# 7seg.net
KiCad netlist of a schematic drawn in Altium Designer
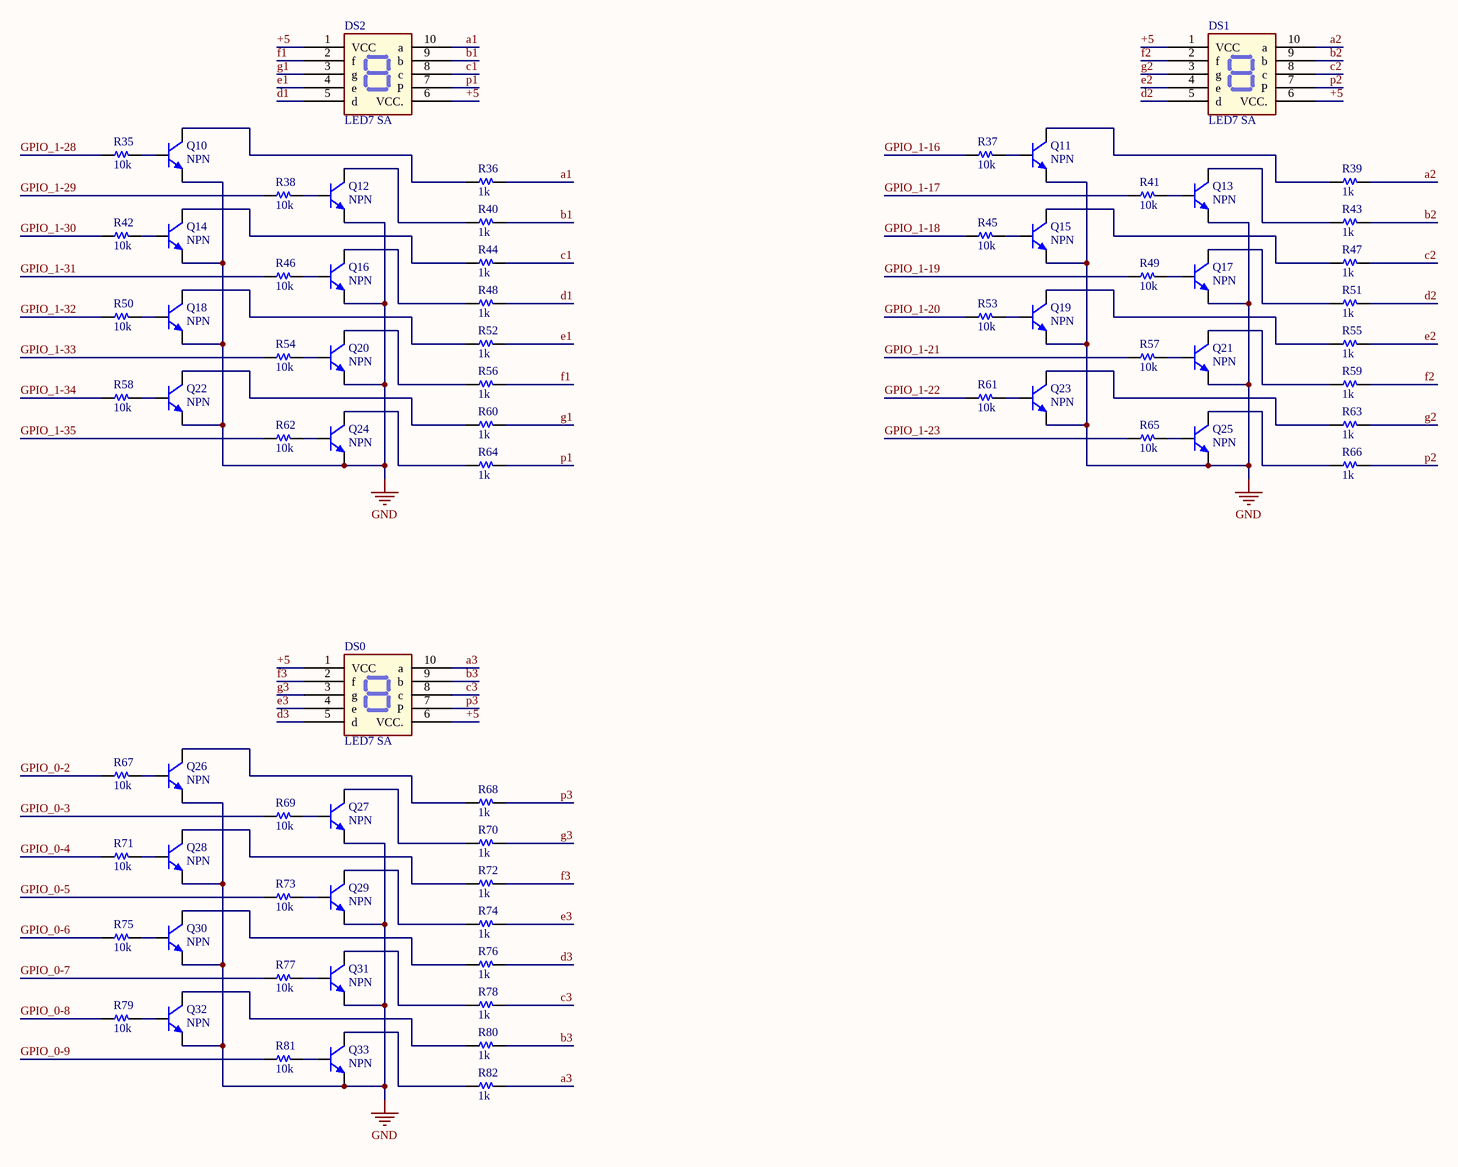
[diagram p0: 7seg.SchDoc]

(export (version "E")
  (design (tool "Eeschema 10.0.6"))
  (components
    (comp (ref "DS0")
      (value "LED7 SA")
      (footprint "Led7seg 0.36in")
      (libsource (lib "chipfc_libs") (part "LED7 SA"))
    )
    (comp (ref "DS1")
      (value "LED7 SA")
      (footprint "Led7seg 0.36in")
      (libsource (lib "chipfc_libs") (part "LED7 SA"))
    )
    (comp (ref "DS2")
      (value "LED7 SA")
      (footprint "Led7seg 0.36in")
      (libsource (lib "chipfc_libs") (part "LED7 SA"))
    )
    (comp (ref "Q10")
      (value "NPN")
      (footprint "SOT-23")
      (description "NPN Bipolar Transistor")
      (libsource (lib "chipfc_libs") (part "Transistor NPN"))
    )
    (comp (ref "Q11")
      (value "NPN")
      (footprint "SOT-23")
      (description "NPN Bipolar Transistor")
      (libsource (lib "chipfc_libs") (part "Transistor NPN"))
    )
    (comp (ref "Q12")
      (value "NPN")
      (footprint "SOT-23")
      (description "NPN Bipolar Transistor")
      (libsource (lib "chipfc_libs") (part "Transistor NPN"))
    )
    (comp (ref "Q13")
      (value "NPN")
      (footprint "SOT-23")
      (description "NPN Bipolar Transistor")
      (libsource (lib "chipfc_libs") (part "Transistor NPN"))
    )
    (comp (ref "Q14")
      (value "NPN")
      (footprint "SOT-23")
      (description "NPN Bipolar Transistor")
      (libsource (lib "chipfc_libs") (part "Transistor NPN"))
    )
    (comp (ref "Q15")
      (value "NPN")
      (footprint "SOT-23")
      (description "NPN Bipolar Transistor")
      (libsource (lib "chipfc_libs") (part "Transistor NPN"))
    )
    (comp (ref "Q16")
      (value "NPN")
      (footprint "SOT-23")
      (description "NPN Bipolar Transistor")
      (libsource (lib "chipfc_libs") (part "Transistor NPN"))
    )
    (comp (ref "Q17")
      (value "NPN")
      (footprint "SOT-23")
      (description "NPN Bipolar Transistor")
      (libsource (lib "chipfc_libs") (part "Transistor NPN"))
    )
    (comp (ref "Q18")
      (value "NPN")
      (footprint "SOT-23")
      (description "NPN Bipolar Transistor")
      (libsource (lib "chipfc_libs") (part "Transistor NPN"))
    )
    (comp (ref "Q19")
      (value "NPN")
      (footprint "SOT-23")
      (description "NPN Bipolar Transistor")
      (libsource (lib "chipfc_libs") (part "Transistor NPN"))
    )
    (comp (ref "Q20")
      (value "NPN")
      (footprint "SOT-23")
      (description "NPN Bipolar Transistor")
      (libsource (lib "chipfc_libs") (part "Transistor NPN"))
    )
    (comp (ref "Q21")
      (value "NPN")
      (footprint "SOT-23")
      (description "NPN Bipolar Transistor")
      (libsource (lib "chipfc_libs") (part "Transistor NPN"))
    )
    (comp (ref "Q22")
      (value "NPN")
      (footprint "SOT-23")
      (description "NPN Bipolar Transistor")
      (libsource (lib "chipfc_libs") (part "Transistor NPN"))
    )
    (comp (ref "Q23")
      (value "NPN")
      (footprint "SOT-23")
      (description "NPN Bipolar Transistor")
      (libsource (lib "chipfc_libs") (part "Transistor NPN"))
    )
    (comp (ref "Q24")
      (value "NPN")
      (footprint "SOT-23")
      (description "NPN Bipolar Transistor")
      (libsource (lib "chipfc_libs") (part "Transistor NPN"))
    )
    (comp (ref "Q25")
      (value "NPN")
      (footprint "SOT-23")
      (description "NPN Bipolar Transistor")
      (libsource (lib "chipfc_libs") (part "Transistor NPN"))
    )
    (comp (ref "Q26")
      (value "NPN")
      (footprint "SOT-23")
      (description "NPN Bipolar Transistor")
      (libsource (lib "chipfc_libs") (part "Transistor NPN"))
    )
    (comp (ref "Q27")
      (value "NPN")
      (footprint "SOT-23")
      (description "NPN Bipolar Transistor")
      (libsource (lib "chipfc_libs") (part "Transistor NPN"))
    )
    (comp (ref "Q28")
      (value "NPN")
      (footprint "SOT-23")
      (description "NPN Bipolar Transistor")
      (libsource (lib "chipfc_libs") (part "Transistor NPN"))
    )
    (comp (ref "Q29")
      (value "NPN")
      (footprint "SOT-23")
      (description "NPN Bipolar Transistor")
      (libsource (lib "chipfc_libs") (part "Transistor NPN"))
    )
    (comp (ref "Q30")
      (value "NPN")
      (footprint "SOT-23")
      (description "NPN Bipolar Transistor")
      (libsource (lib "chipfc_libs") (part "Transistor NPN"))
    )
    (comp (ref "Q31")
      (value "NPN")
      (footprint "SOT-23")
      (description "NPN Bipolar Transistor")
      (libsource (lib "chipfc_libs") (part "Transistor NPN"))
    )
    (comp (ref "Q32")
      (value "NPN")
      (footprint "SOT-23")
      (description "NPN Bipolar Transistor")
      (libsource (lib "chipfc_libs") (part "Transistor NPN"))
    )
    (comp (ref "Q33")
      (value "NPN")
      (footprint "SOT-23")
      (description "NPN Bipolar Transistor")
      (libsource (lib "chipfc_libs") (part "Transistor NPN"))
    )
    (comp (ref "R35")
      (value "10k")
      (footprint "R 0603")
      (description "Resistor")
      (libsource (lib "chipfc_libs") (part "Resistor"))
    )
    (comp (ref "R36")
      (value "1k")
      (footprint "R 0603")
      (description "Resistor")
      (libsource (lib "chipfc_libs") (part "Resistor"))
    )
    (comp (ref "R37")
      (value "10k")
      (footprint "R 0603")
      (description "Resistor")
      (libsource (lib "chipfc_libs") (part "Resistor"))
    )
    (comp (ref "R38")
      (value "10k")
      (footprint "R 0603")
      (description "Resistor")
      (libsource (lib "chipfc_libs") (part "Resistor"))
    )
    (comp (ref "R39")
      (value "1k")
      (footprint "R 0603")
      (description "Resistor")
      (libsource (lib "chipfc_libs") (part "Resistor"))
    )
    (comp (ref "R40")
      (value "1k")
      (footprint "R 0603")
      (description "Resistor")
      (libsource (lib "chipfc_libs") (part "Resistor"))
    )
    (comp (ref "R41")
      (value "10k")
      (footprint "R 0603")
      (description "Resistor")
      (libsource (lib "chipfc_libs") (part "Resistor"))
    )
    (comp (ref "R42")
      (value "10k")
      (footprint "R 0603")
      (description "Resistor")
      (libsource (lib "chipfc_libs") (part "Resistor"))
    )
    (comp (ref "R43")
      (value "1k")
      (footprint "R 0603")
      (description "Resistor")
      (libsource (lib "chipfc_libs") (part "Resistor"))
    )
    (comp (ref "R44")
      (value "1k")
      (footprint "R 0603")
      (description "Resistor")
      (libsource (lib "chipfc_libs") (part "Resistor"))
    )
    (comp (ref "R45")
      (value "10k")
      (footprint "R 0603")
      (description "Resistor")
      (libsource (lib "chipfc_libs") (part "Resistor"))
    )
    (comp (ref "R46")
      (value "10k")
      (footprint "R 0603")
      (description "Resistor")
      (libsource (lib "chipfc_libs") (part "Resistor"))
    )
    (comp (ref "R47")
      (value "1k")
      (footprint "R 0603")
      (description "Resistor")
      (libsource (lib "chipfc_libs") (part "Resistor"))
    )
    (comp (ref "R48")
      (value "1k")
      (footprint "R 0603")
      (description "Resistor")
      (libsource (lib "chipfc_libs") (part "Resistor"))
    )
    (comp (ref "R49")
      (value "10k")
      (footprint "R 0603")
      (description "Resistor")
      (libsource (lib "chipfc_libs") (part "Resistor"))
    )
    (comp (ref "R50")
      (value "10k")
      (footprint "R 0603")
      (description "Resistor")
      (libsource (lib "chipfc_libs") (part "Resistor"))
    )
    (comp (ref "R51")
      (value "1k")
      (footprint "R 0603")
      (description "Resistor")
      (libsource (lib "chipfc_libs") (part "Resistor"))
    )
    (comp (ref "R52")
      (value "1k")
      (footprint "R 0603")
      (description "Resistor")
      (libsource (lib "chipfc_libs") (part "Resistor"))
    )
    (comp (ref "R53")
      (value "10k")
      (footprint "R 0603")
      (description "Resistor")
      (libsource (lib "chipfc_libs") (part "Resistor"))
    )
    (comp (ref "R54")
      (value "10k")
      (footprint "R 0603")
      (description "Resistor")
      (libsource (lib "chipfc_libs") (part "Resistor"))
    )
    (comp (ref "R55")
      (value "1k")
      (footprint "R 0603")
      (description "Resistor")
      (libsource (lib "chipfc_libs") (part "Resistor"))
    )
    (comp (ref "R56")
      (value "1k")
      (footprint "R 0603")
      (description "Resistor")
      (libsource (lib "chipfc_libs") (part "Resistor"))
    )
    (comp (ref "R57")
      (value "10k")
      (footprint "R 0603")
      (description "Resistor")
      (libsource (lib "chipfc_libs") (part "Resistor"))
    )
    (comp (ref "R58")
      (value "10k")
      (footprint "R 0603")
      (description "Resistor")
      (libsource (lib "chipfc_libs") (part "Resistor"))
    )
    (comp (ref "R59")
      (value "1k")
      (footprint "R 0603")
      (description "Resistor")
      (libsource (lib "chipfc_libs") (part "Resistor"))
    )
    (comp (ref "R60")
      (value "1k")
      (footprint "R 0603")
      (description "Resistor")
      (libsource (lib "chipfc_libs") (part "Resistor"))
    )
    (comp (ref "R61")
      (value "10k")
      (footprint "R 0603")
      (description "Resistor")
      (libsource (lib "chipfc_libs") (part "Resistor"))
    )
    (comp (ref "R62")
      (value "10k")
      (footprint "R 0603")
      (description "Resistor")
      (libsource (lib "chipfc_libs") (part "Resistor"))
    )
    (comp (ref "R63")
      (value "1k")
      (footprint "R 0603")
      (description "Resistor")
      (libsource (lib "chipfc_libs") (part "Resistor"))
    )
    (comp (ref "R64")
      (value "1k")
      (footprint "R 0603")
      (description "Resistor")
      (libsource (lib "chipfc_libs") (part "Resistor"))
    )
    (comp (ref "R65")
      (value "10k")
      (footprint "R 0603")
      (description "Resistor")
      (libsource (lib "chipfc_libs") (part "Resistor"))
    )
    (comp (ref "R66")
      (value "1k")
      (footprint "R 0603")
      (description "Resistor")
      (libsource (lib "chipfc_libs") (part "Resistor"))
    )
    (comp (ref "R67")
      (value "10k")
      (footprint "R 0603")
      (description "Resistor")
      (libsource (lib "chipfc_libs") (part "Resistor"))
    )
    (comp (ref "R68")
      (value "1k")
      (footprint "R 0603")
      (description "Resistor")
      (libsource (lib "chipfc_libs") (part "Resistor"))
    )
    (comp (ref "R69")
      (value "10k")
      (footprint "R 0603")
      (description "Resistor")
      (libsource (lib "chipfc_libs") (part "Resistor"))
    )
    (comp (ref "R70")
      (value "1k")
      (footprint "R 0603")
      (description "Resistor")
      (libsource (lib "chipfc_libs") (part "Resistor"))
    )
    (comp (ref "R71")
      (value "10k")
      (footprint "R 0603")
      (description "Resistor")
      (libsource (lib "chipfc_libs") (part "Resistor"))
    )
    (comp (ref "R72")
      (value "1k")
      (footprint "R 0603")
      (description "Resistor")
      (libsource (lib "chipfc_libs") (part "Resistor"))
    )
    (comp (ref "R73")
      (value "10k")
      (footprint "R 0603")
      (description "Resistor")
      (libsource (lib "chipfc_libs") (part "Resistor"))
    )
    (comp (ref "R74")
      (value "1k")
      (footprint "R 0603")
      (description "Resistor")
      (libsource (lib "chipfc_libs") (part "Resistor"))
    )
    (comp (ref "R75")
      (value "10k")
      (footprint "R 0603")
      (description "Resistor")
      (libsource (lib "chipfc_libs") (part "Resistor"))
    )
    (comp (ref "R76")
      (value "1k")
      (footprint "R 0603")
      (description "Resistor")
      (libsource (lib "chipfc_libs") (part "Resistor"))
    )
    (comp (ref "R77")
      (value "10k")
      (footprint "R 0603")
      (description "Resistor")
      (libsource (lib "chipfc_libs") (part "Resistor"))
    )
    (comp (ref "R78")
      (value "1k")
      (footprint "R 0603")
      (description "Resistor")
      (libsource (lib "chipfc_libs") (part "Resistor"))
    )
    (comp (ref "R79")
      (value "10k")
      (footprint "R 0603")
      (description "Resistor")
      (libsource (lib "chipfc_libs") (part "Resistor"))
    )
    (comp (ref "R80")
      (value "1k")
      (footprint "R 0603")
      (description "Resistor")
      (libsource (lib "chipfc_libs") (part "Resistor"))
    )
    (comp (ref "R81")
      (value "10k")
      (footprint "R 0603")
      (description "Resistor")
      (libsource (lib "chipfc_libs") (part "Resistor"))
    )
    (comp (ref "R82")
      (value "1k")
      (footprint "R 0603")
      (description "Resistor")
      (libsource (lib "chipfc_libs") (part "Resistor"))
    )
  )
  (nets
    (net (code "1") (name "/+5") (class "Default")
      (node (ref "DS0") (pin "1") (pinfunction "VCC_1") (pintype "passive"))
      (node (ref "DS0") (pin "6") (pinfunction "VCC._6") (pintype "passive"))
      (node (ref "DS1") (pin "1") (pinfunction "VCC_1") (pintype "passive"))
      (node (ref "DS1") (pin "6") (pinfunction "VCC._6") (pintype "passive"))
      (node (ref "DS2") (pin "1") (pinfunction "VCC_1") (pintype "passive"))
      (node (ref "DS2") (pin "6") (pinfunction "VCC._6") (pintype "passive"))
    )
    (net (code "2") (name "/GPIO_0-2") (class "Default")
      (node (ref "R67") (pin "1") (pinfunction "1_1") (pintype "passive"))
    )
    (net (code "3") (name "/GPIO_0-3") (class "Default")
      (node (ref "R69") (pin "1") (pinfunction "1_1") (pintype "passive"))
    )
    (net (code "4") (name "/GPIO_0-4") (class "Default")
      (node (ref "R71") (pin "1") (pinfunction "1_1") (pintype "passive"))
    )
    (net (code "5") (name "/GPIO_0-5") (class "Default")
      (node (ref "R73") (pin "1") (pinfunction "1_1") (pintype "passive"))
    )
    (net (code "6") (name "/GPIO_0-6") (class "Default")
      (node (ref "R75") (pin "1") (pinfunction "1_1") (pintype "passive"))
    )
    (net (code "7") (name "/GPIO_0-7") (class "Default")
      (node (ref "R77") (pin "1") (pinfunction "1_1") (pintype "passive"))
    )
    (net (code "8") (name "/GPIO_0-8") (class "Default")
      (node (ref "R79") (pin "1") (pinfunction "1_1") (pintype "passive"))
    )
    (net (code "9") (name "/GPIO_0-9") (class "Default")
      (node (ref "R81") (pin "1") (pinfunction "1_1") (pintype "passive"))
    )
    (net (code "10") (name "/GPIO_1-16") (class "Default")
      (node (ref "R37") (pin "1") (pinfunction "1_1") (pintype "passive"))
    )
    (net (code "11") (name "/GPIO_1-17") (class "Default")
      (node (ref "R41") (pin "1") (pinfunction "1_1") (pintype "passive"))
    )
    (net (code "12") (name "/GPIO_1-18") (class "Default")
      (node (ref "R45") (pin "1") (pinfunction "1_1") (pintype "passive"))
    )
    (net (code "13") (name "/GPIO_1-19") (class "Default")
      (node (ref "R49") (pin "1") (pinfunction "1_1") (pintype "passive"))
    )
    (net (code "14") (name "/GPIO_1-20") (class "Default")
      (node (ref "R53") (pin "1") (pinfunction "1_1") (pintype "passive"))
    )
    (net (code "15") (name "/GPIO_1-21") (class "Default")
      (node (ref "R57") (pin "1") (pinfunction "1_1") (pintype "passive"))
    )
    (net (code "16") (name "/GPIO_1-22") (class "Default")
      (node (ref "R61") (pin "1") (pinfunction "1_1") (pintype "passive"))
    )
    (net (code "17") (name "/GPIO_1-23") (class "Default")
      (node (ref "R65") (pin "1") (pinfunction "1_1") (pintype "passive"))
    )
    (net (code "18") (name "/GPIO_1-28") (class "Default")
      (node (ref "R35") (pin "1") (pinfunction "1_1") (pintype "passive"))
    )
    (net (code "19") (name "/GPIO_1-29") (class "Default")
      (node (ref "R38") (pin "1") (pinfunction "1_1") (pintype "passive"))
    )
    (net (code "20") (name "/GPIO_1-30") (class "Default")
      (node (ref "R42") (pin "1") (pinfunction "1_1") (pintype "passive"))
    )
    (net (code "21") (name "/GPIO_1-31") (class "Default")
      (node (ref "R46") (pin "1") (pinfunction "1_1") (pintype "passive"))
    )
    (net (code "22") (name "/GPIO_1-32") (class "Default")
      (node (ref "R50") (pin "1") (pinfunction "1_1") (pintype "passive"))
    )
    (net (code "23") (name "/GPIO_1-33") (class "Default")
      (node (ref "R54") (pin "1") (pinfunction "1_1") (pintype "passive"))
    )
    (net (code "24") (name "/GPIO_1-34") (class "Default")
      (node (ref "R58") (pin "1") (pinfunction "1_1") (pintype "passive"))
    )
    (net (code "25") (name "/GPIO_1-35") (class "Default")
      (node (ref "R62") (pin "1") (pinfunction "1_1") (pintype "passive"))
    )
    (net (code "26") (name "/a1") (class "Default")
      (node (ref "DS2") (pin "10") (pinfunction "a_10") (pintype "passive"))
      (node (ref "R36") (pin "2") (pinfunction "2_2") (pintype "passive"))
    )
    (net (code "27") (name "/a2") (class "Default")
      (node (ref "DS1") (pin "10") (pinfunction "a_10") (pintype "passive"))
      (node (ref "R39") (pin "2") (pinfunction "2_2") (pintype "passive"))
    )
    (net (code "28") (name "/a3") (class "Default")
      (node (ref "DS0") (pin "10") (pinfunction "a_10") (pintype "passive"))
      (node (ref "R82") (pin "2") (pinfunction "2_2") (pintype "passive"))
    )
    (net (code "29") (name "/b1") (class "Default")
      (node (ref "DS2") (pin "9") (pinfunction "b_9") (pintype "passive"))
      (node (ref "R40") (pin "2") (pinfunction "2_2") (pintype "passive"))
    )
    (net (code "30") (name "/b2") (class "Default")
      (node (ref "DS1") (pin "9") (pinfunction "b_9") (pintype "passive"))
      (node (ref "R43") (pin "2") (pinfunction "2_2") (pintype "passive"))
    )
    (net (code "31") (name "/b3") (class "Default")
      (node (ref "DS0") (pin "9") (pinfunction "b_9") (pintype "passive"))
      (node (ref "R80") (pin "2") (pinfunction "2_2") (pintype "passive"))
    )
    (net (code "32") (name "/c1") (class "Default")
      (node (ref "DS2") (pin "8") (pinfunction "c_8") (pintype "passive"))
      (node (ref "R44") (pin "2") (pinfunction "2_2") (pintype "passive"))
    )
    (net (code "33") (name "/c2") (class "Default")
      (node (ref "DS1") (pin "8") (pinfunction "c_8") (pintype "passive"))
      (node (ref "R47") (pin "2") (pinfunction "2_2") (pintype "passive"))
    )
    (net (code "34") (name "/c3") (class "Default")
      (node (ref "DS0") (pin "8") (pinfunction "c_8") (pintype "passive"))
      (node (ref "R78") (pin "2") (pinfunction "2_2") (pintype "passive"))
    )
    (net (code "35") (name "/d1") (class "Default")
      (node (ref "DS2") (pin "5") (pinfunction "d_5") (pintype "passive"))
      (node (ref "R48") (pin "2") (pinfunction "2_2") (pintype "passive"))
    )
    (net (code "36") (name "/d2") (class "Default")
      (node (ref "DS1") (pin "5") (pinfunction "d_5") (pintype "passive"))
      (node (ref "R51") (pin "2") (pinfunction "2_2") (pintype "passive"))
    )
    (net (code "37") (name "/d3") (class "Default")
      (node (ref "DS0") (pin "5") (pinfunction "d_5") (pintype "passive"))
      (node (ref "R76") (pin "2") (pinfunction "2_2") (pintype "passive"))
    )
    (net (code "38") (name "/e1") (class "Default")
      (node (ref "DS2") (pin "4") (pinfunction "e_4") (pintype "passive"))
      (node (ref "R52") (pin "2") (pinfunction "2_2") (pintype "passive"))
    )
    (net (code "39") (name "/e2") (class "Default")
      (node (ref "DS1") (pin "4") (pinfunction "e_4") (pintype "passive"))
      (node (ref "R55") (pin "2") (pinfunction "2_2") (pintype "passive"))
    )
    (net (code "40") (name "/e3") (class "Default")
      (node (ref "DS0") (pin "4") (pinfunction "e_4") (pintype "passive"))
      (node (ref "R74") (pin "2") (pinfunction "2_2") (pintype "passive"))
    )
    (net (code "41") (name "/f1") (class "Default")
      (node (ref "DS2") (pin "2") (pinfunction "f_2") (pintype "passive"))
      (node (ref "R56") (pin "2") (pinfunction "2_2") (pintype "passive"))
    )
    (net (code "42") (name "/f2") (class "Default")
      (node (ref "DS1") (pin "2") (pinfunction "f_2") (pintype "passive"))
      (node (ref "R59") (pin "2") (pinfunction "2_2") (pintype "passive"))
    )
    (net (code "43") (name "/f3") (class "Default")
      (node (ref "DS0") (pin "2") (pinfunction "f_2") (pintype "passive"))
      (node (ref "R72") (pin "2") (pinfunction "2_2") (pintype "passive"))
    )
    (net (code "44") (name "/g1") (class "Default")
      (node (ref "DS2") (pin "3") (pinfunction "g_3") (pintype "passive"))
      (node (ref "R60") (pin "2") (pinfunction "2_2") (pintype "passive"))
    )
    (net (code "45") (name "/g2") (class "Default")
      (node (ref "DS1") (pin "3") (pinfunction "g_3") (pintype "passive"))
      (node (ref "R63") (pin "2") (pinfunction "2_2") (pintype "passive"))
    )
    (net (code "46") (name "/g3") (class "Default")
      (node (ref "DS0") (pin "3") (pinfunction "g_3") (pintype "passive"))
      (node (ref "R70") (pin "2") (pinfunction "2_2") (pintype "passive"))
    )
    (net (code "47") (name "/p1") (class "Default")
      (node (ref "DS2") (pin "7") (pinfunction "P_7") (pintype "passive"))
      (node (ref "R64") (pin "2") (pinfunction "2_2") (pintype "passive"))
    )
    (net (code "48") (name "/p2") (class "Default")
      (node (ref "DS1") (pin "7") (pinfunction "P_7") (pintype "passive"))
      (node (ref "R66") (pin "2") (pinfunction "2_2") (pintype "passive"))
    )
    (net (code "49") (name "/p3") (class "Default")
      (node (ref "DS0") (pin "7") (pinfunction "P_7") (pintype "passive"))
      (node (ref "R68") (pin "2") (pinfunction "2_2") (pintype "passive"))
    )
    (net (code "50") (name "GND") (class "Default")
      (node (ref "Q10") (pin "2") (pinfunction "E_2") (pintype "passive"))
      (node (ref "Q11") (pin "2") (pinfunction "E_2") (pintype "passive"))
      (node (ref "Q12") (pin "2") (pinfunction "E_2") (pintype "passive"))
      (node (ref "Q13") (pin "2") (pinfunction "E_2") (pintype "passive"))
      (node (ref "Q14") (pin "2") (pinfunction "E_2") (pintype "passive"))
      (node (ref "Q15") (pin "2") (pinfunction "E_2") (pintype "passive"))
      (node (ref "Q16") (pin "2") (pinfunction "E_2") (pintype "passive"))
      (node (ref "Q17") (pin "2") (pinfunction "E_2") (pintype "passive"))
      (node (ref "Q18") (pin "2") (pinfunction "E_2") (pintype "passive"))
      (node (ref "Q19") (pin "2") (pinfunction "E_2") (pintype "passive"))
      (node (ref "Q20") (pin "2") (pinfunction "E_2") (pintype "passive"))
      (node (ref "Q21") (pin "2") (pinfunction "E_2") (pintype "passive"))
      (node (ref "Q22") (pin "2") (pinfunction "E_2") (pintype "passive"))
      (node (ref "Q23") (pin "2") (pinfunction "E_2") (pintype "passive"))
      (node (ref "Q24") (pin "2") (pinfunction "E_2") (pintype "passive"))
      (node (ref "Q25") (pin "2") (pinfunction "E_2") (pintype "passive"))
      (node (ref "Q26") (pin "2") (pinfunction "E_2") (pintype "passive"))
      (node (ref "Q27") (pin "2") (pinfunction "E_2") (pintype "passive"))
      (node (ref "Q28") (pin "2") (pinfunction "E_2") (pintype "passive"))
      (node (ref "Q29") (pin "2") (pinfunction "E_2") (pintype "passive"))
      (node (ref "Q30") (pin "2") (pinfunction "E_2") (pintype "passive"))
      (node (ref "Q31") (pin "2") (pinfunction "E_2") (pintype "passive"))
      (node (ref "Q32") (pin "2") (pinfunction "E_2") (pintype "passive"))
      (node (ref "Q33") (pin "2") (pinfunction "E_2") (pintype "passive"))
    )
    (net (code "51") (name "Net-(Q10-B)") (class "Default")
      (node (ref "Q10") (pin "1") (pinfunction "B_1") (pintype "passive"))
      (node (ref "R35") (pin "2") (pinfunction "2_2") (pintype "passive"))
    )
    (net (code "52") (name "Net-(Q10-C)") (class "Default")
      (node (ref "Q10") (pin "3") (pinfunction "C_3") (pintype "passive"))
      (node (ref "R36") (pin "1") (pinfunction "1_1") (pintype "passive"))
    )
    (net (code "53") (name "Net-(Q11-B)") (class "Default")
      (node (ref "Q11") (pin "1") (pinfunction "B_1") (pintype "passive"))
      (node (ref "R37") (pin "2") (pinfunction "2_2") (pintype "passive"))
    )
    (net (code "54") (name "Net-(Q11-C)") (class "Default")
      (node (ref "Q11") (pin "3") (pinfunction "C_3") (pintype "passive"))
      (node (ref "R39") (pin "1") (pinfunction "1_1") (pintype "passive"))
    )
    (net (code "55") (name "Net-(Q12-B)") (class "Default")
      (node (ref "Q12") (pin "1") (pinfunction "B_1") (pintype "passive"))
      (node (ref "R38") (pin "2") (pinfunction "2_2") (pintype "passive"))
    )
    (net (code "56") (name "Net-(Q12-C)") (class "Default")
      (node (ref "Q12") (pin "3") (pinfunction "C_3") (pintype "passive"))
      (node (ref "R40") (pin "1") (pinfunction "1_1") (pintype "passive"))
    )
    (net (code "57") (name "Net-(Q13-B)") (class "Default")
      (node (ref "Q13") (pin "1") (pinfunction "B_1") (pintype "passive"))
      (node (ref "R41") (pin "2") (pinfunction "2_2") (pintype "passive"))
    )
    (net (code "58") (name "Net-(Q13-C)") (class "Default")
      (node (ref "Q13") (pin "3") (pinfunction "C_3") (pintype "passive"))
      (node (ref "R43") (pin "1") (pinfunction "1_1") (pintype "passive"))
    )
    (net (code "59") (name "Net-(Q14-B)") (class "Default")
      (node (ref "Q14") (pin "1") (pinfunction "B_1") (pintype "passive"))
      (node (ref "R42") (pin "2") (pinfunction "2_2") (pintype "passive"))
    )
    (net (code "60") (name "Net-(Q14-C)") (class "Default")
      (node (ref "Q14") (pin "3") (pinfunction "C_3") (pintype "passive"))
      (node (ref "R44") (pin "1") (pinfunction "1_1") (pintype "passive"))
    )
    (net (code "61") (name "Net-(Q15-B)") (class "Default")
      (node (ref "Q15") (pin "1") (pinfunction "B_1") (pintype "passive"))
      (node (ref "R45") (pin "2") (pinfunction "2_2") (pintype "passive"))
    )
    (net (code "62") (name "Net-(Q15-C)") (class "Default")
      (node (ref "Q15") (pin "3") (pinfunction "C_3") (pintype "passive"))
      (node (ref "R47") (pin "1") (pinfunction "1_1") (pintype "passive"))
    )
    (net (code "63") (name "Net-(Q16-B)") (class "Default")
      (node (ref "Q16") (pin "1") (pinfunction "B_1") (pintype "passive"))
      (node (ref "R46") (pin "2") (pinfunction "2_2") (pintype "passive"))
    )
    (net (code "64") (name "Net-(Q16-C)") (class "Default")
      (node (ref "Q16") (pin "3") (pinfunction "C_3") (pintype "passive"))
      (node (ref "R48") (pin "1") (pinfunction "1_1") (pintype "passive"))
    )
    (net (code "65") (name "Net-(Q17-B)") (class "Default")
      (node (ref "Q17") (pin "1") (pinfunction "B_1") (pintype "passive"))
      (node (ref "R49") (pin "2") (pinfunction "2_2") (pintype "passive"))
    )
    (net (code "66") (name "Net-(Q17-C)") (class "Default")
      (node (ref "Q17") (pin "3") (pinfunction "C_3") (pintype "passive"))
      (node (ref "R51") (pin "1") (pinfunction "1_1") (pintype "passive"))
    )
    (net (code "67") (name "Net-(Q18-B)") (class "Default")
      (node (ref "Q18") (pin "1") (pinfunction "B_1") (pintype "passive"))
      (node (ref "R50") (pin "2") (pinfunction "2_2") (pintype "passive"))
    )
    (net (code "68") (name "Net-(Q18-C)") (class "Default")
      (node (ref "Q18") (pin "3") (pinfunction "C_3") (pintype "passive"))
      (node (ref "R52") (pin "1") (pinfunction "1_1") (pintype "passive"))
    )
    (net (code "69") (name "Net-(Q19-B)") (class "Default")
      (node (ref "Q19") (pin "1") (pinfunction "B_1") (pintype "passive"))
      (node (ref "R53") (pin "2") (pinfunction "2_2") (pintype "passive"))
    )
    (net (code "70") (name "Net-(Q19-C)") (class "Default")
      (node (ref "Q19") (pin "3") (pinfunction "C_3") (pintype "passive"))
      (node (ref "R55") (pin "1") (pinfunction "1_1") (pintype "passive"))
    )
    (net (code "71") (name "Net-(Q20-B)") (class "Default")
      (node (ref "Q20") (pin "1") (pinfunction "B_1") (pintype "passive"))
      (node (ref "R54") (pin "2") (pinfunction "2_2") (pintype "passive"))
    )
    (net (code "72") (name "Net-(Q20-C)") (class "Default")
      (node (ref "Q20") (pin "3") (pinfunction "C_3") (pintype "passive"))
      (node (ref "R56") (pin "1") (pinfunction "1_1") (pintype "passive"))
    )
    (net (code "73") (name "Net-(Q21-B)") (class "Default")
      (node (ref "Q21") (pin "1") (pinfunction "B_1") (pintype "passive"))
      (node (ref "R57") (pin "2") (pinfunction "2_2") (pintype "passive"))
    )
    (net (code "74") (name "Net-(Q21-C)") (class "Default")
      (node (ref "Q21") (pin "3") (pinfunction "C_3") (pintype "passive"))
      (node (ref "R59") (pin "1") (pinfunction "1_1") (pintype "passive"))
    )
    (net (code "75") (name "Net-(Q22-B)") (class "Default")
      (node (ref "Q22") (pin "1") (pinfunction "B_1") (pintype "passive"))
      (node (ref "R58") (pin "2") (pinfunction "2_2") (pintype "passive"))
    )
    (net (code "76") (name "Net-(Q22-C)") (class "Default")
      (node (ref "Q22") (pin "3") (pinfunction "C_3") (pintype "passive"))
      (node (ref "R60") (pin "1") (pinfunction "1_1") (pintype "passive"))
    )
    (net (code "77") (name "Net-(Q23-B)") (class "Default")
      (node (ref "Q23") (pin "1") (pinfunction "B_1") (pintype "passive"))
      (node (ref "R61") (pin "2") (pinfunction "2_2") (pintype "passive"))
    )
    (net (code "78") (name "Net-(Q23-C)") (class "Default")
      (node (ref "Q23") (pin "3") (pinfunction "C_3") (pintype "passive"))
      (node (ref "R63") (pin "1") (pinfunction "1_1") (pintype "passive"))
    )
    (net (code "79") (name "Net-(Q24-B)") (class "Default")
      (node (ref "Q24") (pin "1") (pinfunction "B_1") (pintype "passive"))
      (node (ref "R62") (pin "2") (pinfunction "2_2") (pintype "passive"))
    )
    (net (code "80") (name "Net-(Q24-C)") (class "Default")
      (node (ref "Q24") (pin "3") (pinfunction "C_3") (pintype "passive"))
      (node (ref "R64") (pin "1") (pinfunction "1_1") (pintype "passive"))
    )
    (net (code "81") (name "Net-(Q25-B)") (class "Default")
      (node (ref "Q25") (pin "1") (pinfunction "B_1") (pintype "passive"))
      (node (ref "R65") (pin "2") (pinfunction "2_2") (pintype "passive"))
    )
    (net (code "82") (name "Net-(Q25-C)") (class "Default")
      (node (ref "Q25") (pin "3") (pinfunction "C_3") (pintype "passive"))
      (node (ref "R66") (pin "1") (pinfunction "1_1") (pintype "passive"))
    )
    (net (code "83") (name "Net-(Q26-B)") (class "Default")
      (node (ref "Q26") (pin "1") (pinfunction "B_1") (pintype "passive"))
      (node (ref "R67") (pin "2") (pinfunction "2_2") (pintype "passive"))
    )
    (net (code "84") (name "Net-(Q26-C)") (class "Default")
      (node (ref "Q26") (pin "3") (pinfunction "C_3") (pintype "passive"))
      (node (ref "R68") (pin "1") (pinfunction "1_1") (pintype "passive"))
    )
    (net (code "85") (name "Net-(Q27-B)") (class "Default")
      (node (ref "Q27") (pin "1") (pinfunction "B_1") (pintype "passive"))
      (node (ref "R69") (pin "2") (pinfunction "2_2") (pintype "passive"))
    )
    (net (code "86") (name "Net-(Q27-C)") (class "Default")
      (node (ref "Q27") (pin "3") (pinfunction "C_3") (pintype "passive"))
      (node (ref "R70") (pin "1") (pinfunction "1_1") (pintype "passive"))
    )
    (net (code "87") (name "Net-(Q28-B)") (class "Default")
      (node (ref "Q28") (pin "1") (pinfunction "B_1") (pintype "passive"))
      (node (ref "R71") (pin "2") (pinfunction "2_2") (pintype "passive"))
    )
    (net (code "88") (name "Net-(Q28-C)") (class "Default")
      (node (ref "Q28") (pin "3") (pinfunction "C_3") (pintype "passive"))
      (node (ref "R72") (pin "1") (pinfunction "1_1") (pintype "passive"))
    )
    (net (code "89") (name "Net-(Q29-B)") (class "Default")
      (node (ref "Q29") (pin "1") (pinfunction "B_1") (pintype "passive"))
      (node (ref "R73") (pin "2") (pinfunction "2_2") (pintype "passive"))
    )
    (net (code "90") (name "Net-(Q29-C)") (class "Default")
      (node (ref "Q29") (pin "3") (pinfunction "C_3") (pintype "passive"))
      (node (ref "R74") (pin "1") (pinfunction "1_1") (pintype "passive"))
    )
    (net (code "91") (name "Net-(Q30-B)") (class "Default")
      (node (ref "Q30") (pin "1") (pinfunction "B_1") (pintype "passive"))
      (node (ref "R75") (pin "2") (pinfunction "2_2") (pintype "passive"))
    )
    (net (code "92") (name "Net-(Q30-C)") (class "Default")
      (node (ref "Q30") (pin "3") (pinfunction "C_3") (pintype "passive"))
      (node (ref "R76") (pin "1") (pinfunction "1_1") (pintype "passive"))
    )
    (net (code "93") (name "Net-(Q31-B)") (class "Default")
      (node (ref "Q31") (pin "1") (pinfunction "B_1") (pintype "passive"))
      (node (ref "R77") (pin "2") (pinfunction "2_2") (pintype "passive"))
    )
    (net (code "94") (name "Net-(Q31-C)") (class "Default")
      (node (ref "Q31") (pin "3") (pinfunction "C_3") (pintype "passive"))
      (node (ref "R78") (pin "1") (pinfunction "1_1") (pintype "passive"))
    )
    (net (code "95") (name "Net-(Q32-B)") (class "Default")
      (node (ref "Q32") (pin "1") (pinfunction "B_1") (pintype "passive"))
      (node (ref "R79") (pin "2") (pinfunction "2_2") (pintype "passive"))
    )
    (net (code "96") (name "Net-(Q32-C)") (class "Default")
      (node (ref "Q32") (pin "3") (pinfunction "C_3") (pintype "passive"))
      (node (ref "R80") (pin "1") (pinfunction "1_1") (pintype "passive"))
    )
    (net (code "97") (name "Net-(Q33-B)") (class "Default")
      (node (ref "Q33") (pin "1") (pinfunction "B_1") (pintype "passive"))
      (node (ref "R81") (pin "2") (pinfunction "2_2") (pintype "passive"))
    )
    (net (code "98") (name "Net-(Q33-C)") (class "Default")
      (node (ref "Q33") (pin "3") (pinfunction "C_3") (pintype "passive"))
      (node (ref "R82") (pin "1") (pinfunction "1_1") (pintype "passive"))
    )
  )
)
